# LED_BAR.net
KiCad netlist of a schematic drawn in EAGLE
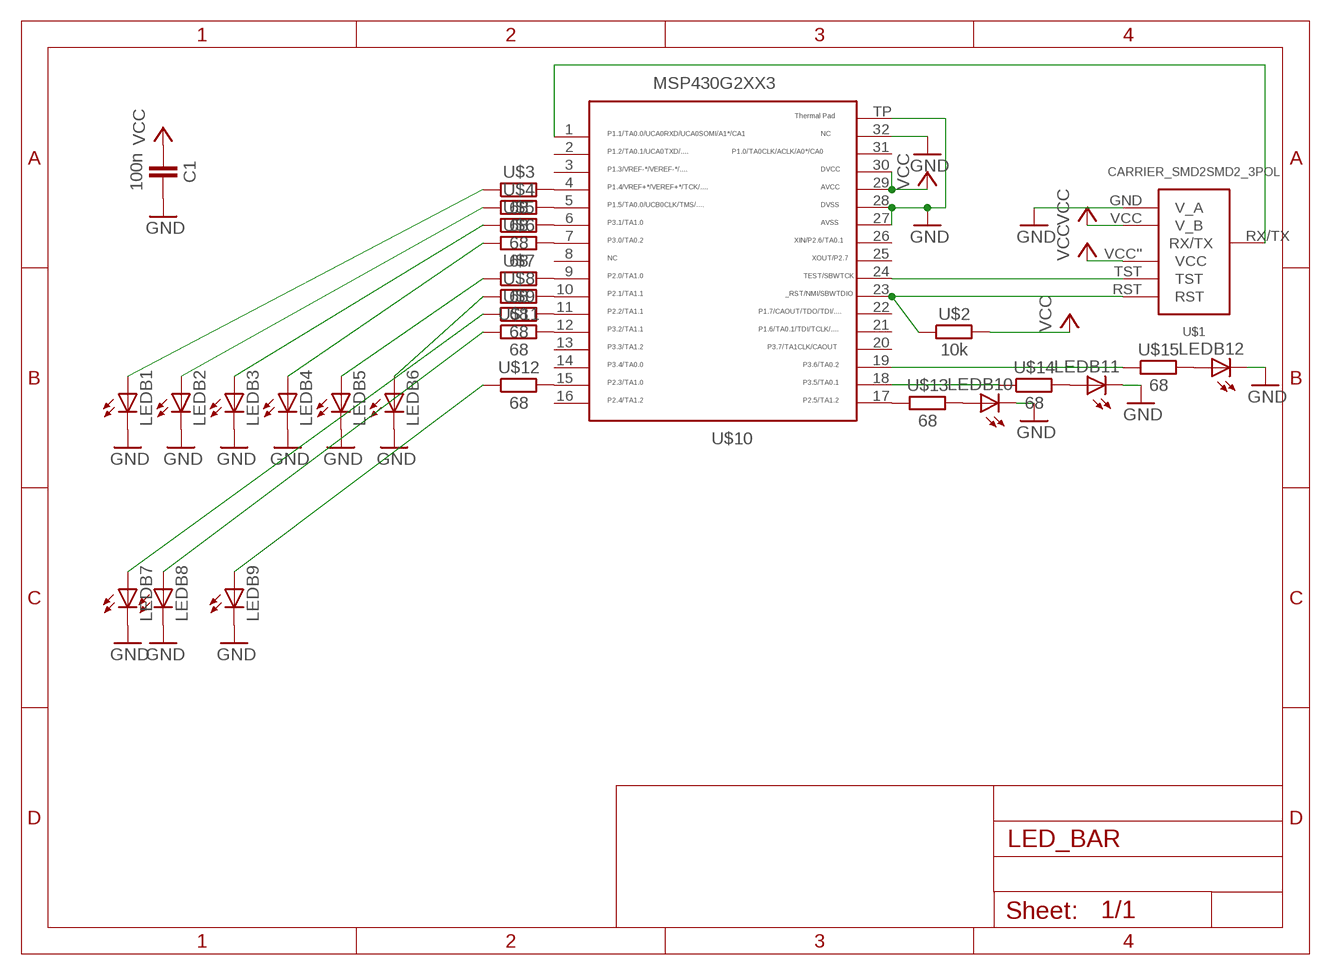
[diagram p0: schematic, sheet 1]

(export (version "E")
  (design (tool "Eeschema 10.0.6"))
  (components
    (comp (ref "C1")
      (value "100n")
      (footprint "eagle-import:603")
      (libsource (lib "eagle-import") (part "CAPACITOR"))
    )
    (comp (ref "LEDB1")
      (value "LEDCHIPLED_0603")
      (footprint "eagle-import:CHIPLED_0603")
      (libsource (lib "eagle-import") (part "LEDCHIPLED_0603"))
    )
    (comp (ref "LEDB2")
      (value "LEDCHIPLED_0603")
      (footprint "eagle-import:CHIPLED_0603")
      (libsource (lib "eagle-import") (part "LEDCHIPLED_0603"))
    )
    (comp (ref "LEDB3")
      (value "LEDCHIPLED_0603")
      (footprint "eagle-import:CHIPLED_0603")
      (libsource (lib "eagle-import") (part "LEDCHIPLED_0603"))
    )
    (comp (ref "LEDB4")
      (value "LEDCHIPLED_0603")
      (footprint "eagle-import:CHIPLED_0603")
      (libsource (lib "eagle-import") (part "LEDCHIPLED_0603"))
    )
    (comp (ref "LEDB5")
      (value "LEDCHIPLED_0603")
      (footprint "eagle-import:CHIPLED_0603")
      (libsource (lib "eagle-import") (part "LEDCHIPLED_0603"))
    )
    (comp (ref "LEDB6")
      (value "LEDCHIPLED_0603")
      (footprint "eagle-import:CHIPLED_0603")
      (libsource (lib "eagle-import") (part "LEDCHIPLED_0603"))
    )
    (comp (ref "LEDB7")
      (value "LEDCHIPLED_0603")
      (footprint "eagle-import:CHIPLED_0603")
      (libsource (lib "eagle-import") (part "LEDCHIPLED_0603"))
    )
    (comp (ref "LEDB8")
      (value "LEDCHIPLED_0603")
      (footprint "eagle-import:CHIPLED_0603")
      (libsource (lib "eagle-import") (part "LEDCHIPLED_0603"))
    )
    (comp (ref "LEDB9")
      (value "LEDCHIPLED_0603")
      (footprint "eagle-import:CHIPLED_0603")
      (libsource (lib "eagle-import") (part "LEDCHIPLED_0603"))
    )
    (comp (ref "LEDB10")
      (value "LEDCHIPLED_0603")
      (footprint "eagle-import:CHIPLED_0603")
      (libsource (lib "eagle-import") (part "LEDCHIPLED_0603"))
    )
    (comp (ref "LEDB11")
      (value "LEDCHIPLED_0603")
      (footprint "eagle-import:CHIPLED_0603")
      (libsource (lib "eagle-import") (part "LEDCHIPLED_0603"))
    )
    (comp (ref "LEDB12")
      (value "LEDCHIPLED_0603")
      (footprint "eagle-import:CHIPLED_0603")
      (libsource (lib "eagle-import") (part "LEDCHIPLED_0603"))
    )
    (comp (ref "U$1")
      (value "CARRIER_SMD2SMD2_3POL")
      (footprint "eagle-import:CARRIER_SMD2_3POL")
      (libsource (lib "eagle-import") (part "CARRIER_SMD2SMD2_3POL"))
    )
    (comp (ref "U$2")
      (value "10k")
      (footprint "eagle-import:603")
      (libsource (lib "eagle-import") (part "RESISTOR0603"))
    )
    (comp (ref "U$3")
      (value "68")
      (footprint "eagle-import:603")
      (libsource (lib "eagle-import") (part "RESISTOR0603"))
    )
    (comp (ref "U$4")
      (value "68")
      (footprint "eagle-import:603")
      (libsource (lib "eagle-import") (part "RESISTOR0603"))
    )
    (comp (ref "U$5")
      (value "68")
      (footprint "eagle-import:603")
      (libsource (lib "eagle-import") (part "RESISTOR0603"))
    )
    (comp (ref "U$6")
      (value "68")
      (footprint "eagle-import:603")
      (libsource (lib "eagle-import") (part "RESISTOR0603"))
    )
    (comp (ref "U$7")
      (value "68")
      (footprint "eagle-import:603")
      (libsource (lib "eagle-import") (part "RESISTOR0603"))
    )
    (comp (ref "U$8")
      (value "68")
      (footprint "eagle-import:603")
      (libsource (lib "eagle-import") (part "RESISTOR0603"))
    )
    (comp (ref "U$9")
      (value "68")
      (footprint "eagle-import:603")
      (libsource (lib "eagle-import") (part "RESISTOR0603"))
    )
    (comp (ref "U$10")
      (value "MSP430G2553")
      (footprint "eagle-import:QFN32")
      (libsource (lib "eagle-import") (part "MSP430G2553"))
    )
    (comp (ref "U$11")
      (value "68")
      (footprint "eagle-import:603")
      (libsource (lib "eagle-import") (part "RESISTOR0603"))
    )
    (comp (ref "U$12")
      (value "68")
      (footprint "eagle-import:603")
      (libsource (lib "eagle-import") (part "RESISTOR0603"))
    )
    (comp (ref "U$13")
      (value "68")
      (footprint "eagle-import:603")
      (libsource (lib "eagle-import") (part "RESISTOR0603"))
    )
    (comp (ref "U$14")
      (value "68")
      (footprint "eagle-import:603")
      (libsource (lib "eagle-import") (part "RESISTOR0603"))
    )
    (comp (ref "U$15")
      (value "68")
      (footprint "eagle-import:603")
      (libsource (lib "eagle-import") (part "RESISTOR0603"))
    )
  )
  (nets
    (net (code "1") (name "GND") (class "Default")
      (node (ref "C1") (pin "2") (pinfunction "2_2") (pintype "passive"))
      (node (ref "LEDB1") (pin "C") (pinfunction "C_C") (pintype "passive"))
      (node (ref "LEDB10") (pin "C") (pinfunction "C_C") (pintype "passive"))
      (node (ref "LEDB11") (pin "C") (pinfunction "C_C") (pintype "passive"))
      (node (ref "LEDB12") (pin "C") (pinfunction "C_C") (pintype "passive"))
      (node (ref "LEDB2") (pin "C") (pinfunction "C_C") (pintype "passive"))
      (node (ref "LEDB3") (pin "C") (pinfunction "C_C") (pintype "passive"))
      (node (ref "LEDB4") (pin "C") (pinfunction "C_C") (pintype "passive"))
      (node (ref "LEDB5") (pin "C") (pinfunction "C_C") (pintype "passive"))
      (node (ref "LEDB6") (pin "C") (pinfunction "C_C") (pintype "passive"))
      (node (ref "LEDB7") (pin "C") (pinfunction "C_C") (pintype "passive"))
      (node (ref "LEDB8") (pin "C") (pinfunction "C_C") (pintype "passive"))
      (node (ref "LEDB9") (pin "C") (pinfunction "C_C") (pintype "passive"))
      (node (ref "U$1") (pin "GND") (pinfunction "V_A_GND") (pintype "bidirectional"))
      (node (ref "U$10") (pin "27") (pinfunction "27_27") (pintype "bidirectional"))
      (node (ref "U$10") (pin "28") (pinfunction "28_28") (pintype "bidirectional"))
      (node (ref "U$10") (pin "32") (pinfunction "32_32") (pintype "bidirectional"))
      (node (ref "U$10") (pin "TP") (pinfunction "TP_TP") (pintype "bidirectional"))
    )
    (net (code "2") (name "Net-(LEDB1-PadA)") (class "Default")
      (node (ref "LEDB1") (pin "A") (pinfunction "A_A") (pintype "passive"))
      (node (ref "U$3") (pin "1") (pinfunction "1_1") (pintype "passive"))
    )
    (net (code "3") (name "Net-(LEDB2-PadA)") (class "Default")
      (node (ref "LEDB2") (pin "A") (pinfunction "A_A") (pintype "passive"))
      (node (ref "U$4") (pin "1") (pinfunction "1_1") (pintype "passive"))
    )
    (net (code "4") (name "Net-(LEDB3-PadA)") (class "Default")
      (node (ref "LEDB3") (pin "A") (pinfunction "A_A") (pintype "passive"))
      (node (ref "U$5") (pin "1") (pinfunction "1_1") (pintype "passive"))
    )
    (net (code "5") (name "Net-(LEDB4-PadA)") (class "Default")
      (node (ref "LEDB4") (pin "A") (pinfunction "A_A") (pintype "passive"))
      (node (ref "U$6") (pin "1") (pinfunction "1_1") (pintype "passive"))
    )
    (net (code "6") (name "Net-(LEDB5-PadA)") (class "Default")
      (node (ref "LEDB5") (pin "A") (pinfunction "A_A") (pintype "passive"))
      (node (ref "U$7") (pin "1") (pinfunction "1_1") (pintype "passive"))
    )
    (net (code "7") (name "Net-(LEDB6-PadA)") (class "Default")
      (node (ref "LEDB6") (pin "A") (pinfunction "A_A") (pintype "passive"))
      (node (ref "U$8") (pin "1") (pinfunction "1_1") (pintype "passive"))
    )
    (net (code "8") (name "Net-(LEDB7-PadA)") (class "Default")
      (node (ref "LEDB7") (pin "A") (pinfunction "A_A") (pintype "passive"))
      (node (ref "U$9") (pin "1") (pinfunction "1_1") (pintype "passive"))
    )
    (net (code "9") (name "Net-(LEDB8-PadA)") (class "Default")
      (node (ref "LEDB8") (pin "A") (pinfunction "A_A") (pintype "passive"))
      (node (ref "U$11") (pin "1") (pinfunction "1_1") (pintype "passive"))
    )
    (net (code "10") (name "Net-(LEDB9-PadA)") (class "Default")
      (node (ref "LEDB9") (pin "A") (pinfunction "A_A") (pintype "passive"))
      (node (ref "U$12") (pin "1") (pinfunction "1_1") (pintype "passive"))
    )
    (net (code "11") (name "Net-(LEDB10-PadA)") (class "Default")
      (node (ref "LEDB10") (pin "A") (pinfunction "A_A") (pintype "passive"))
      (node (ref "U$13") (pin "2") (pinfunction "2_2") (pintype "passive"))
    )
    (net (code "12") (name "Net-(LEDB11-PadA)") (class "Default")
      (node (ref "LEDB11") (pin "A") (pinfunction "A_A") (pintype "passive"))
      (node (ref "U$14") (pin "2") (pinfunction "2_2") (pintype "passive"))
    )
    (net (code "13") (name "Net-(LEDB12-PadA)") (class "Default")
      (node (ref "LEDB12") (pin "A") (pinfunction "A_A") (pintype "passive"))
      (node (ref "U$15") (pin "2") (pinfunction "2_2") (pintype "passive"))
    )
    (net (code "14") (name "Net-(U$1-PadRST)") (class "Default")
      (node (ref "U$1") (pin "RST") (pinfunction "RST_RST") (pintype "bidirectional"))
      (node (ref "U$10") (pin "23") (pinfunction "23_23") (pintype "bidirectional"))
      (node (ref "U$2") (pin "1") (pinfunction "1_1") (pintype "passive"))
    )
    (net (code "15") (name "Net-(U$1-PadRX{slash}TX)") (class "Default")
      (node (ref "U$1") (pin "RX/TX") (pinfunction "RX/TX_RX/TX") (pintype "bidirectional"))
      (node (ref "U$10") (pin "1") (pinfunction "1_1") (pintype "bidirectional"))
    )
    (net (code "16") (name "Net-(U$1-PadTST)") (class "Default")
      (node (ref "U$1") (pin "TST") (pinfunction "TST_TST") (pintype "bidirectional"))
      (node (ref "U$10") (pin "24") (pinfunction "24_24") (pintype "bidirectional"))
    )
    (net (code "17") (name "Net-(U$10-Pad4)") (class "Default")
      (node (ref "U$10") (pin "4") (pinfunction "4_4") (pintype "bidirectional"))
      (node (ref "U$3") (pin "2") (pinfunction "2_2") (pintype "passive"))
    )
    (net (code "18") (name "Net-(U$10-Pad5)") (class "Default")
      (node (ref "U$10") (pin "5") (pinfunction "5_5") (pintype "bidirectional"))
      (node (ref "U$4") (pin "2") (pinfunction "2_2") (pintype "passive"))
    )
    (net (code "19") (name "Net-(U$10-Pad6)") (class "Default")
      (node (ref "U$10") (pin "6") (pinfunction "6_6") (pintype "bidirectional"))
      (node (ref "U$5") (pin "2") (pinfunction "2_2") (pintype "passive"))
    )
    (net (code "20") (name "Net-(U$10-Pad7)") (class "Default")
      (node (ref "U$10") (pin "7") (pinfunction "7_7") (pintype "bidirectional"))
      (node (ref "U$6") (pin "2") (pinfunction "2_2") (pintype "passive"))
    )
    (net (code "21") (name "Net-(U$10-Pad9)") (class "Default")
      (node (ref "U$10") (pin "9") (pinfunction "9_9") (pintype "bidirectional"))
      (node (ref "U$7") (pin "2") (pinfunction "2_2") (pintype "passive"))
    )
    (net (code "22") (name "Net-(U$10-Pad10)") (class "Default")
      (node (ref "U$10") (pin "10") (pinfunction "10_10") (pintype "bidirectional"))
      (node (ref "U$8") (pin "2") (pinfunction "2_2") (pintype "passive"))
    )
    (net (code "23") (name "Net-(U$10-Pad11)") (class "Default")
      (node (ref "U$10") (pin "11") (pinfunction "11_11") (pintype "bidirectional"))
      (node (ref "U$9") (pin "2") (pinfunction "2_2") (pintype "passive"))
    )
    (net (code "24") (name "Net-(U$10-Pad12)") (class "Default")
      (node (ref "U$10") (pin "12") (pinfunction "12_12") (pintype "bidirectional"))
      (node (ref "U$11") (pin "2") (pinfunction "2_2") (pintype "passive"))
    )
    (net (code "25") (name "Net-(U$10-Pad15)") (class "Default")
      (node (ref "U$10") (pin "15") (pinfunction "15_15") (pintype "bidirectional"))
      (node (ref "U$12") (pin "2") (pinfunction "2_2") (pintype "passive"))
    )
    (net (code "26") (name "Net-(U$10-Pad17)") (class "Default")
      (node (ref "U$10") (pin "17") (pinfunction "17_17") (pintype "bidirectional"))
      (node (ref "U$13") (pin "1") (pinfunction "1_1") (pintype "passive"))
    )
    (net (code "27") (name "Net-(U$10-Pad18)") (class "Default")
      (node (ref "U$10") (pin "18") (pinfunction "18_18") (pintype "bidirectional"))
      (node (ref "U$14") (pin "1") (pinfunction "1_1") (pintype "passive"))
    )
    (net (code "28") (name "Net-(U$10-Pad19)") (class "Default")
      (node (ref "U$10") (pin "19") (pinfunction "19_19") (pintype "bidirectional"))
      (node (ref "U$15") (pin "1") (pinfunction "1_1") (pintype "passive"))
    )
    (net (code "29") (name "VCC") (class "Default")
      (node (ref "C1") (pin "1") (pinfunction "1_1") (pintype "passive"))
      (node (ref "U$1") (pin "VCC") (pinfunction "V_B_VCC") (pintype "bidirectional"))
      (node (ref "U$1") (pin "VCC''") (pinfunction "VCC_VCC''") (pintype "bidirectional"))
      (node (ref "U$10") (pin "29") (pinfunction "29_29") (pintype "bidirectional"))
      (node (ref "U$10") (pin "30") (pinfunction "30_30") (pintype "bidirectional"))
      (node (ref "U$2") (pin "2") (pinfunction "2_2") (pintype "passive"))
    )
    (net (code "30") (name "unconnected-(U$10-Pad2)") (class "Default")
      (node (ref "U$10") (pin "2") (pinfunction "2_2") (pintype "bidirectional"))
    )
    (net (code "31") (name "unconnected-(U$10-Pad3)") (class "Default")
      (node (ref "U$10") (pin "3") (pinfunction "3_3") (pintype "bidirectional"))
    )
    (net (code "32") (name "unconnected-(U$10-Pad8)") (class "Default")
      (node (ref "U$10") (pin "8") (pinfunction "8_8") (pintype "bidirectional"))
    )
    (net (code "33") (name "unconnected-(U$10-Pad13)") (class "Default")
      (node (ref "U$10") (pin "13") (pinfunction "13_13") (pintype "bidirectional"))
    )
    (net (code "34") (name "unconnected-(U$10-Pad14)") (class "Default")
      (node (ref "U$10") (pin "14") (pinfunction "14_14") (pintype "bidirectional"))
    )
    (net (code "35") (name "unconnected-(U$10-Pad16)") (class "Default")
      (node (ref "U$10") (pin "16") (pinfunction "16_16") (pintype "bidirectional"))
    )
    (net (code "36") (name "unconnected-(U$10-Pad20)") (class "Default")
      (node (ref "U$10") (pin "20") (pinfunction "20_20") (pintype "bidirectional"))
    )
    (net (code "37") (name "unconnected-(U$10-Pad21)") (class "Default")
      (node (ref "U$10") (pin "21") (pinfunction "21_21") (pintype "bidirectional"))
    )
    (net (code "38") (name "unconnected-(U$10-Pad22)") (class "Default")
      (node (ref "U$10") (pin "22") (pinfunction "22_22") (pintype "bidirectional"))
    )
    (net (code "39") (name "unconnected-(U$10-Pad25)") (class "Default")
      (node (ref "U$10") (pin "25") (pinfunction "25_25") (pintype "bidirectional"))
    )
    (net (code "40") (name "unconnected-(U$10-Pad26)") (class "Default")
      (node (ref "U$10") (pin "26") (pinfunction "26_26") (pintype "bidirectional"))
    )
    (net (code "41") (name "unconnected-(U$10-Pad31)") (class "Default")
      (node (ref "U$10") (pin "31") (pinfunction "31_31") (pintype "bidirectional"))
    )
  )
)
